# MCU_CH340.net
KiCad netlist of a schematic drawn in Altium Designer
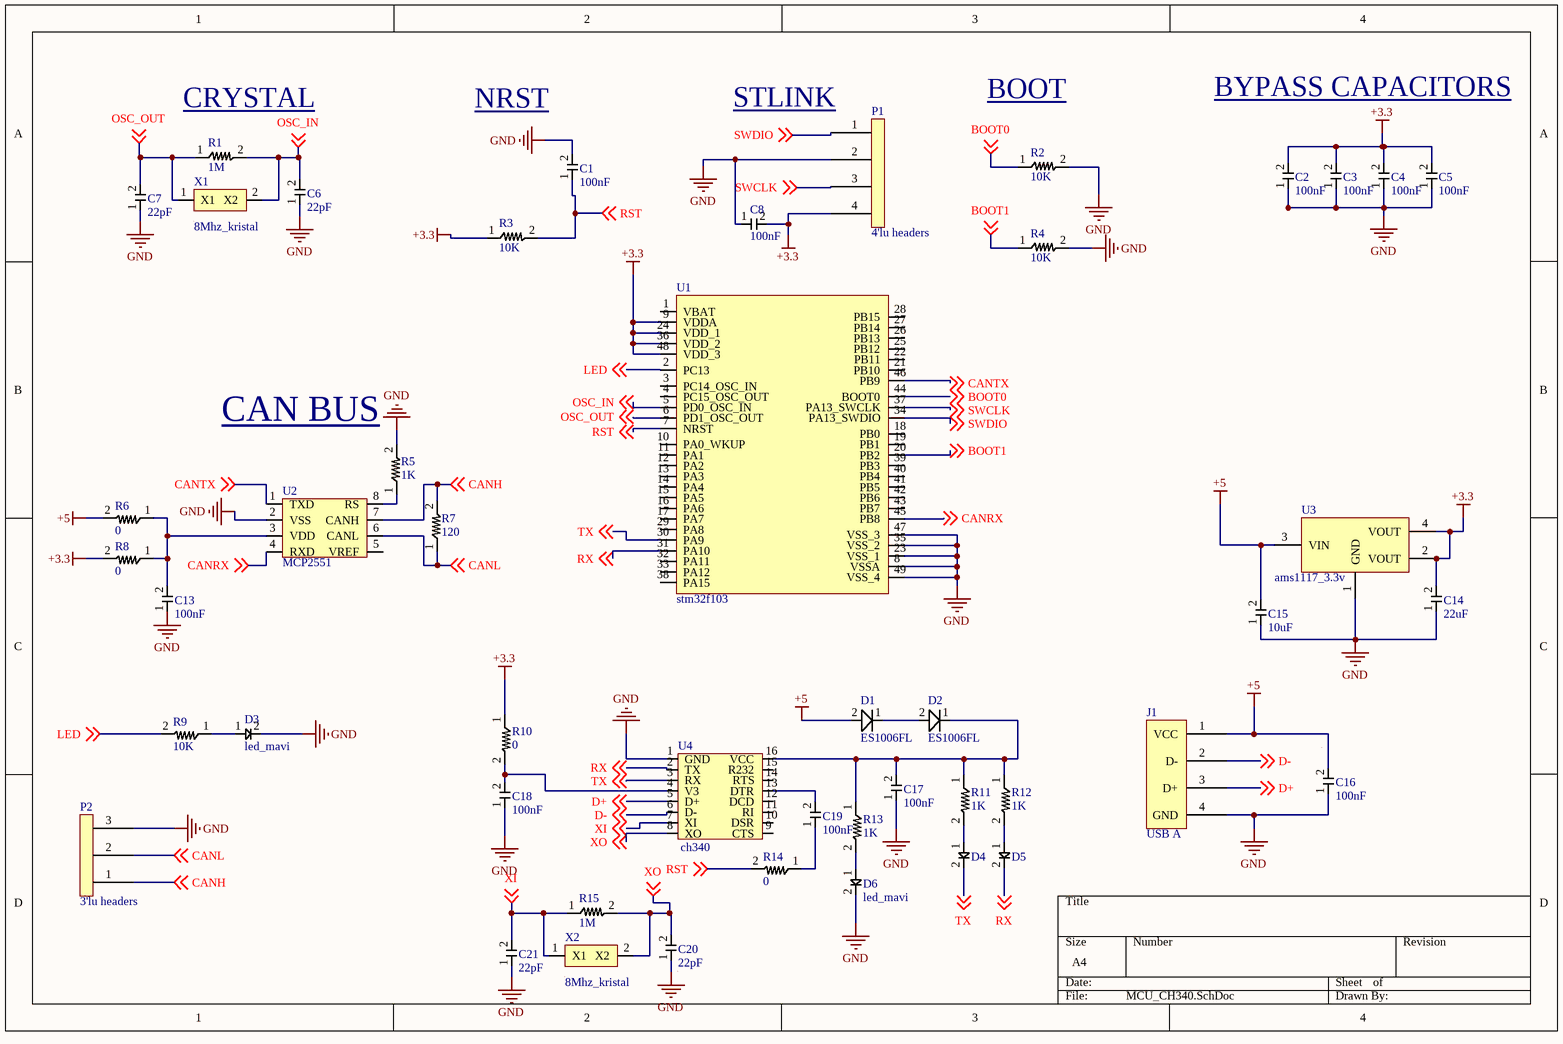
[diagram p0: MCU_CH340.SchDoc]

(export (version "E")
  (design (tool "Eeschema 10.0.6"))
  (components
    (comp (ref "C1")
      (value "100nF")
      (footprint "0805_CAP")
      (description "0805 CAPACITOR")
      (libsource (lib "smd_kompenent") (part "0805_CAP"))
    )
    (comp (ref "C2")
      (value "100nF")
      (footprint "0805_CAP")
      (description "0805 CAPACITOR")
      (libsource (lib "smd_kompenent") (part "0805_CAP"))
    )
    (comp (ref "C3")
      (value "100nF")
      (footprint "0805_CAP")
      (description "0805 CAPACITOR")
      (libsource (lib "smd_kompenent") (part "0805_CAP"))
    )
    (comp (ref "C4")
      (value "100nF")
      (footprint "0805_CAP")
      (description "0805 CAPACITOR")
      (libsource (lib "smd_kompenent") (part "0805_CAP"))
    )
    (comp (ref "C5")
      (value "100nF")
      (footprint "0805_CAP")
      (description "0805 CAPACITOR")
      (libsource (lib "smd_kompenent") (part "0805_CAP"))
    )
    (comp (ref "C6")
      (value "22pF")
      (footprint "0805_CAP")
      (description "0805 CAPACITOR")
      (libsource (lib "smd_kompenent") (part "0805_CAP"))
    )
    (comp (ref "C7")
      (value "22pF")
      (footprint "0805_CAP")
      (description "0805 CAPACITOR")
      (libsource (lib "smd_kompenent") (part "0805_CAP"))
    )
    (comp (ref "C8")
      (value "100nF")
      (footprint "0805_CAP")
      (description "0805 CAPACITOR")
      (libsource (lib "smd_kompenent") (part "0805_CAP"))
    )
    (comp (ref "C13")
      (value "100nF")
      (footprint "0805_CAP")
      (description "0805 CAPACITOR")
      (libsource (lib "smd_kompenent") (part "0805_CAP"))
    )
    (comp (ref "C14")
      (value "22uF")
      (footprint "0805_CAP")
      (description "0805 CAPACITOR")
      (libsource (lib "smd_kompenent") (part "0805_CAP"))
    )
    (comp (ref "C15")
      (value "10uF")
      (footprint "0805_CAP")
      (description "0805 CAPACITOR")
      (libsource (lib "smd_kompenent") (part "0805_CAP"))
    )
    (comp (ref "C16")
      (value "100nF")
      (footprint "0805_CAP")
      (description "0805 CAPACITOR")
      (libsource (lib "smd_kompenent") (part "0805_CAP"))
    )
    (comp (ref "C17")
      (value "100nF")
      (footprint "0805_CAP")
      (description "0805 CAPACITOR")
      (libsource (lib "smd_kompenent") (part "0805_CAP"))
    )
    (comp (ref "C18")
      (value "100nF")
      (footprint "0805_CAP")
      (description "0805 CAPACITOR")
      (libsource (lib "smd_kompenent") (part "0805_CAP"))
    )
    (comp (ref "C19")
      (value "100nF")
      (footprint "0805_CAP")
      (description "0805 CAPACITOR")
      (libsource (lib "smd_kompenent") (part "0805_CAP"))
    )
    (comp (ref "C20")
      (value "22pF")
      (footprint "0805_CAP")
      (description "0805 CAPACITOR")
      (libsource (lib "smd_kompenent") (part "0805_CAP"))
    )
    (comp (ref "C21")
      (value "22pF")
      (footprint "0805_CAP")
      (description "0805 CAPACITOR")
      (libsource (lib "smd_kompenent") (part "0805_CAP"))
    )
    (comp (ref "D1")
      (value "ES1006FL")
      (footprint "ES1006FL")
      (description "ES1006FL 1A 600V Diyot Fred Ultra Hızlı")
      (libsource (lib "smd_kompenent") (part "ES1006FL"))
    )
    (comp (ref "D2")
      (value "ES1006FL")
      (footprint "ES1006FL")
      (description "ES1006FL 1A 600V Diyot Fred Ultra Hızlı")
      (libsource (lib "smd_kompenent") (part "ES1006FL"))
    )
    (comp (ref "D3")
      (value "led_mavi")
      (footprint "led")
      (description "0805 mavi led")
      (libsource (lib "smd_kompenent") (part "led_mavi"))
    )
    (comp (ref "D4")
      (value "~")
      (footprint "led")
      (description "0805 mavi led")
      (libsource (lib "smd_kompenent") (part "led_mavi"))
    )
    (comp (ref "D5")
      (value "~")
      (footprint "led")
      (description "0805 mavi led")
      (libsource (lib "smd_kompenent") (part "led_mavi"))
    )
    (comp (ref "D6")
      (value "led_mavi")
      (footprint "led")
      (description "0805 mavi led")
      (libsource (lib "smd_kompenent") (part "led_mavi"))
    )
    (comp (ref "J1") (value "USB A") (footprint "USB A") (libsource (lib "dip_kompenent") (part "USB A")))
    (comp (ref "P1")
      (value "4'lu headers")
      (footprint "4'lu headers")
      (libsource (lib "dip_kompenent") (part "4'lu headers"))
    )
    (comp (ref "P2")
      (value "3'lu headers")
      (footprint "3'lu headers")
      (libsource (lib "dip_kompenent") (part "3'lu headers"))
    )
    (comp (ref "R1")
      (value "1M")
      (footprint "res_0805")
      (description "0805")
      (libsource (lib "smd_kompenent") (part "0805_RES"))
    )
    (comp (ref "R2")
      (value "10K")
      (footprint "res_0805")
      (description "0805")
      (libsource (lib "smd_kompenent") (part "0805_RES"))
    )
    (comp (ref "R3")
      (value "10K")
      (footprint "res_0805")
      (description "0805")
      (libsource (lib "smd_kompenent") (part "0805_RES"))
    )
    (comp (ref "R4")
      (value "10K")
      (footprint "res_0805")
      (description "0805")
      (libsource (lib "smd_kompenent") (part "0805_RES"))
    )
    (comp (ref "R5")
      (value "1K")
      (footprint "res_0805")
      (description "0805")
      (libsource (lib "smd_kompenent") (part "0805_RES"))
    )
    (comp (ref "R6")
      (value "0")
      (footprint "res_0805")
      (description "0805")
      (libsource (lib "smd_kompenent") (part "0805_RES"))
    )
    (comp (ref "R7")
      (value "120")
      (footprint "res_0805")
      (description "0805")
      (libsource (lib "smd_kompenent") (part "0805_RES"))
    )
    (comp (ref "R8")
      (value "0")
      (footprint "res_0805")
      (description "0805")
      (libsource (lib "smd_kompenent") (part "0805_RES"))
    )
    (comp (ref "R9")
      (value "10K")
      (footprint "res_0805")
      (description "0805")
      (libsource (lib "smd_kompenent") (part "0805_RES"))
    )
    (comp (ref "R10")
      (value "0")
      (footprint "res_0805")
      (description "0805")
      (libsource (lib "smd_kompenent") (part "0805_RES"))
    )
    (comp (ref "R11")
      (value "1K")
      (footprint "res_0805")
      (description "0805")
      (libsource (lib "smd_kompenent") (part "0805_RES"))
    )
    (comp (ref "R12")
      (value "1K")
      (footprint "res_0805")
      (description "0805")
      (libsource (lib "smd_kompenent") (part "0805_RES"))
    )
    (comp (ref "R13")
      (value "1K")
      (footprint "res_0805")
      (description "0805")
      (libsource (lib "smd_kompenent") (part "0805_RES"))
    )
    (comp (ref "R14")
      (value "0")
      (footprint "res_0805")
      (description "0805")
      (libsource (lib "smd_kompenent") (part "0805_RES"))
    )
    (comp (ref "R15")
      (value "1M")
      (footprint "res_0805")
      (description "0805")
      (libsource (lib "smd_kompenent") (part "0805_RES"))
    )
    (comp (ref "U1")
      (value "stm32f103")
      (footprint "STM32F103C6T8")
      (description "STM MCU")
      (libsource (lib "smd_kompenent") (part "stm32f103"))
    )
    (comp (ref "U2")
      (value "MCP2551")
      (footprint "SOIC-8")
      (description "SOIC-8")
      (libsource (lib "smd_kompenent") (part "MCP2551"))
    )
    (comp (ref "U3")
      (value "ams1117_3.3v")
      (footprint "ams1117")
      (libsource (lib "smd_kompenent") (part "ams1117_3.3v"))
    )
    (comp (ref "U4")
      (value "ch340")
      (footprint "CH340 SOIC16")
      (libsource (lib "smd_kompenent") (part "ch340"))
    )
    (comp (ref "X1")
      (value "8Mhz_kristal")
      (footprint "8mhz_kristal")
      (description "2 pin kristal")
      (libsource (lib "smd_kompenent") (part "8Mhz_kristal"))
    )
    (comp (ref "X2")
      (value "8Mhz_kristal")
      (footprint "8mhz_kristal")
      (description "2 pin kristal")
      (libsource (lib "smd_kompenent") (part "8Mhz_kristal"))
    )
  )
  (nets
    (net (code "1") (name "+3.3") (class "Default")
      (node (ref "C14") (pin "2") (pintype "passive"))
      (node (ref "C2") (pin "2") (pintype "passive"))
      (node (ref "C3") (pin "2") (pintype "passive"))
      (node (ref "C4") (pin "2") (pintype "passive"))
      (node (ref "C5") (pin "2") (pintype "passive"))
      (node (ref "C8") (pin "2") (pintype "passive"))
      (node (ref "P1") (pin "4") (pintype "passive"))
      (node (ref "R10") (pin "1") (pintype "passive"))
      (node (ref "R3") (pin "1") (pintype "passive"))
      (node (ref "R8") (pin "2") (pintype "passive"))
      (node (ref "U1") (pin "24") (pinfunction "VDD_1_24") (pintype "passive"))
      (node (ref "U1") (pin "36") (pinfunction "VDD_2_36") (pintype "passive"))
      (node (ref "U1") (pin "48") (pinfunction "VDD_3_48") (pintype "passive"))
      (node (ref "U1") (pin "9") (pinfunction "VDDA_9") (pintype "passive"))
      (node (ref "U3") (pin "2") (pinfunction "VOUT_2") (pintype "passive"))
      (node (ref "U3") (pin "4") (pinfunction "VOUT_4") (pintype "passive"))
    )
    (net (code "2") (name "+5") (class "Default")
      (node (ref "C15") (pin "2") (pintype "passive"))
      (node (ref "C16") (pin "2") (pintype "passive"))
      (node (ref "D1") (pin "2") (pintype "passive"))
      (node (ref "J1") (pin "1") (pinfunction "VCC_1") (pintype "passive"))
      (node (ref "R6") (pin "2") (pintype "passive"))
      (node (ref "U3") (pin "3") (pinfunction "VIN_3") (pintype "passive"))
    )
    (net (code "3") (name "BOOT0") (class "Default")
      (node (ref "R2") (pin "1") (pintype "passive"))
      (node (ref "U1") (pin "44") (pinfunction "BOOT0_44") (pintype "passive"))
    )
    (net (code "4") (name "BOOT1") (class "Default")
      (node (ref "R4") (pin "1") (pintype "passive"))
      (node (ref "U1") (pin "20") (pinfunction "PB2_20") (pintype "passive"))
    )
    (net (code "5") (name "CANH") (class "Default")
      (node (ref "P2") (pin "1") (pintype "passive"))
      (node (ref "R7") (pin "2") (pintype "passive"))
      (node (ref "U2") (pin "7") (pinfunction "CANH_7") (pintype "passive"))
    )
    (net (code "6") (name "CANL") (class "Default")
      (node (ref "P2") (pin "2") (pintype "passive"))
      (node (ref "R7") (pin "1") (pintype "passive"))
      (node (ref "U2") (pin "6") (pinfunction "CANL_6") (pintype "passive"))
    )
    (net (code "7") (name "CANRX") (class "Default")
      (node (ref "U1") (pin "45") (pinfunction "PB8_45") (pintype "passive"))
      (node (ref "U2") (pin "4") (pinfunction "RXD_4") (pintype "passive"))
    )
    (net (code "8") (name "CANTX") (class "Default")
      (node (ref "U1") (pin "46") (pinfunction "PB9_46") (pintype "passive"))
      (node (ref "U2") (pin "1") (pinfunction "TXD_1") (pintype "passive"))
    )
    (net (code "9") (name "D+") (class "Default")
      (node (ref "J1") (pin "3") (pinfunction "D+_3") (pintype "passive"))
      (node (ref "U4") (pin "5") (pinfunction "D+_5") (pintype "passive"))
    )
    (net (code "10") (name "D-") (class "Default")
      (node (ref "J1") (pin "2") (pinfunction "D-_2") (pintype "passive"))
      (node (ref "U4") (pin "6") (pinfunction "D-_6") (pintype "passive"))
    )
    (net (code "11") (name "GND") (class "Default")
      (node (ref "C1") (pin "2") (pintype "passive"))
      (node (ref "C13") (pin "1") (pintype "passive"))
      (node (ref "C14") (pin "1") (pintype "passive"))
      (node (ref "C15") (pin "1") (pintype "passive"))
      (node (ref "C16") (pin "1") (pintype "passive"))
      (node (ref "C17") (pin "1") (pintype "passive"))
      (node (ref "C18") (pin "1") (pintype "passive"))
      (node (ref "C2") (pin "1") (pintype "passive"))
      (node (ref "C20") (pin "1") (pintype "passive"))
      (node (ref "C21") (pin "1") (pintype "passive"))
      (node (ref "C3") (pin "1") (pintype "passive"))
      (node (ref "C4") (pin "1") (pintype "passive"))
      (node (ref "C5") (pin "1") (pintype "passive"))
      (node (ref "C6") (pin "1") (pintype "passive"))
      (node (ref "C7") (pin "1") (pintype "passive"))
      (node (ref "C8") (pin "1") (pintype "passive"))
      (node (ref "D3") (pin "2") (pintype "passive"))
      (node (ref "D6") (pin "2") (pintype "passive"))
      (node (ref "J1") (pin "4") (pinfunction "GND_4") (pintype "passive"))
      (node (ref "P1") (pin "2") (pintype "passive"))
      (node (ref "P2") (pin "3") (pintype "passive"))
      (node (ref "R2") (pin "2") (pintype "passive"))
      (node (ref "R4") (pin "2") (pintype "passive"))
      (node (ref "R5") (pin "2") (pintype "passive"))
      (node (ref "U1") (pin "23") (pinfunction "VSS_1_23") (pintype "passive"))
      (node (ref "U1") (pin "35") (pinfunction "VSS_2_35") (pintype "passive"))
      (node (ref "U1") (pin "47") (pinfunction "VSS_3_47") (pintype "passive"))
      (node (ref "U1") (pin "49") (pinfunction "VSS_4_49") (pintype "passive"))
      (node (ref "U1") (pin "8") (pinfunction "VSSA_8") (pintype "passive"))
      (node (ref "U2") (pin "2") (pinfunction "VSS_2") (pintype "passive"))
      (node (ref "U3") (pin "1") (pinfunction "GND_1") (pintype "passive"))
      (node (ref "U4") (pin "1") (pinfunction "GND_1") (pintype "passive"))
    )
    (net (code "12") (name "LED") (class "Default")
      (node (ref "R9") (pin "2") (pintype "passive"))
      (node (ref "U1") (pin "2") (pinfunction "PC13_2") (pintype "passive"))
    )
    (net (code "13") (name "Net-(C19-Pad1)") (class "Default")
      (node (ref "C19") (pin "1") (pintype "passive"))
      (node (ref "R14") (pin "1") (pintype "passive"))
    )
    (net (code "14") (name "Net-(D1-Pad1)") (class "Default")
      (node (ref "D1") (pin "1") (pintype "passive"))
      (node (ref "D2") (pin "2") (pintype "passive"))
    )
    (net (code "15") (name "Net-(D3-Pad1)") (class "Default")
      (node (ref "D3") (pin "1") (pintype "passive"))
      (node (ref "R9") (pin "1") (pintype "passive"))
    )
    (net (code "16") (name "Net-(D4-Pad1)") (class "Default")
      (node (ref "D4") (pin "1") (pintype "passive"))
      (node (ref "R11") (pin "2") (pintype "passive"))
    )
    (net (code "17") (name "Net-(D5-Pad1)") (class "Default")
      (node (ref "D5") (pin "1") (pintype "passive"))
      (node (ref "R12") (pin "2") (pintype "passive"))
    )
    (net (code "18") (name "Net-(D6-Pad1)") (class "Default")
      (node (ref "D6") (pin "1") (pintype "passive"))
      (node (ref "R13") (pin "2") (pintype "passive"))
    )
    (net (code "19") (name "Net-(U2-RS)") (class "Default")
      (node (ref "R5") (pin "1") (pintype "passive"))
      (node (ref "U2") (pin "8") (pinfunction "RS_8") (pintype "passive"))
    )
    (net (code "20") (name "Net-(U2-VDD)") (class "Default")
      (node (ref "C13") (pin "2") (pintype "passive"))
      (node (ref "R6") (pin "1") (pintype "passive"))
      (node (ref "R8") (pin "1") (pintype "passive"))
      (node (ref "U2") (pin "3") (pinfunction "VDD_3") (pintype "passive"))
    )
    (net (code "21") (name "Net-(U4-DTR)") (class "Default")
      (node (ref "C19") (pin "2") (pintype "passive"))
      (node (ref "U4") (pin "13") (pinfunction "DTR_13") (pintype "passive"))
    )
    (net (code "22") (name "Net-(U4-V3)") (class "Default")
      (node (ref "C18") (pin "2") (pintype "passive"))
      (node (ref "R10") (pin "2") (pintype "passive"))
      (node (ref "U4") (pin "4") (pinfunction "V3_4") (pintype "passive"))
    )
    (net (code "23") (name "Net-(U4-VCC)") (class "Default")
      (node (ref "C17") (pin "2") (pintype "passive"))
      (node (ref "D2") (pin "1") (pintype "passive"))
      (node (ref "R11") (pin "1") (pintype "passive"))
      (node (ref "R12") (pin "1") (pintype "passive"))
      (node (ref "R13") (pin "1") (pintype "passive"))
      (node (ref "U4") (pin "16") (pinfunction "VCC_16") (pintype "passive"))
    )
    (net (code "24") (name "OSC_IN") (class "Default")
      (node (ref "C6") (pin "2") (pintype "passive"))
      (node (ref "R1") (pin "2") (pintype "passive"))
      (node (ref "U1") (pin "5") (pinfunction "PD0_OSC_IN_5") (pintype "passive"))
      (node (ref "X1") (pin "2") (pinfunction "X2_2") (pintype "passive"))
    )
    (net (code "25") (name "OSC_OUT") (class "Default")
      (node (ref "C7") (pin "2") (pintype "passive"))
      (node (ref "R1") (pin "1") (pintype "passive"))
      (node (ref "U1") (pin "6") (pinfunction "PD1_OSC_OUT_6") (pintype "passive"))
      (node (ref "X1") (pin "1") (pinfunction "X1_1") (pintype "passive"))
    )
    (net (code "26") (name "RST") (class "Default")
      (node (ref "C1") (pin "1") (pintype "passive"))
      (node (ref "R14") (pin "2") (pintype "passive"))
      (node (ref "R3") (pin "2") (pintype "passive"))
      (node (ref "U1") (pin "7") (pinfunction "NRST_7") (pintype "passive"))
    )
    (net (code "27") (name "RX") (class "Default")
      (node (ref "D5") (pin "2") (pintype "passive"))
      (node (ref "U1") (pin "31") (pinfunction "PA10_31") (pintype "passive"))
      (node (ref "U4") (pin "2") (pinfunction "TX_2") (pintype "passive"))
    )
    (net (code "28") (name "SWCLK") (class "Default")
      (node (ref "P1") (pin "3") (pintype "passive"))
      (node (ref "U1") (pin "37") (pinfunction "PA13_SWCLK_37") (pintype "passive"))
    )
    (net (code "29") (name "SWDIO") (class "Default")
      (node (ref "P1") (pin "1") (pintype "passive"))
      (node (ref "U1") (pin "34") (pinfunction "PA13_SWDIO_34") (pintype "passive"))
    )
    (net (code "30") (name "TX") (class "Default")
      (node (ref "D4") (pin "2") (pintype "passive"))
      (node (ref "U1") (pin "30") (pinfunction "PA9_30") (pintype "passive"))
      (node (ref "U4") (pin "3") (pinfunction "RX_3") (pintype "passive"))
    )
    (net (code "31") (name "XI") (class "Default")
      (node (ref "C21") (pin "2") (pintype "passive"))
      (node (ref "R15") (pin "1") (pintype "passive"))
      (node (ref "U4") (pin "7") (pinfunction "XI_7") (pintype "passive"))
      (node (ref "X2") (pin "1") (pinfunction "X1_1") (pintype "passive"))
    )
    (net (code "32") (name "XO") (class "Default")
      (node (ref "C20") (pin "2") (pintype "passive"))
      (node (ref "R15") (pin "2") (pintype "passive"))
      (node (ref "U4") (pin "8") (pinfunction "XO_8") (pintype "passive"))
      (node (ref "X2") (pin "2") (pinfunction "X2_2") (pintype "passive"))
    )
    (net (code "33") (name "unconnected-(U1-PA0_WKUP-Pad10)") (class "Default")
      (node (ref "U1") (pin "10") (pinfunction "PA0_WKUP_10") (pintype "passive"))
    )
    (net (code "34") (name "unconnected-(U1-PA1-Pad11)") (class "Default")
      (node (ref "U1") (pin "11") (pinfunction "PA1_11") (pintype "passive"))
    )
    (net (code "35") (name "unconnected-(U1-PA2-Pad12)") (class "Default")
      (node (ref "U1") (pin "12") (pinfunction "PA2_12") (pintype "passive"))
    )
    (net (code "36") (name "unconnected-(U1-PA3-Pad13)") (class "Default")
      (node (ref "U1") (pin "13") (pinfunction "PA3_13") (pintype "passive"))
    )
    (net (code "37") (name "unconnected-(U1-PA4-Pad14)") (class "Default")
      (node (ref "U1") (pin "14") (pinfunction "PA4_14") (pintype "passive"))
    )
    (net (code "38") (name "unconnected-(U1-PA5-Pad15)") (class "Default")
      (node (ref "U1") (pin "15") (pinfunction "PA5_15") (pintype "passive"))
    )
    (net (code "39") (name "unconnected-(U1-PA6-Pad16)") (class "Default")
      (node (ref "U1") (pin "16") (pinfunction "PA6_16") (pintype "passive"))
    )
    (net (code "40") (name "unconnected-(U1-PA7-Pad17)") (class "Default")
      (node (ref "U1") (pin "17") (pinfunction "PA7_17") (pintype "passive"))
    )
    (net (code "41") (name "unconnected-(U1-PA8-Pad29)") (class "Default")
      (node (ref "U1") (pin "29") (pinfunction "PA8_29") (pintype "passive"))
    )
    (net (code "42") (name "unconnected-(U1-PA11-Pad32)") (class "Default")
      (node (ref "U1") (pin "32") (pinfunction "PA11_32") (pintype "passive"))
    )
    (net (code "43") (name "unconnected-(U1-PA12-Pad33)") (class "Default")
      (node (ref "U1") (pin "33") (pinfunction "PA12_33") (pintype "passive"))
    )
    (net (code "44") (name "unconnected-(U1-PA15-Pad38)") (class "Default")
      (node (ref "U1") (pin "38") (pinfunction "PA15_38") (pintype "passive"))
    )
    (net (code "45") (name "unconnected-(U1-PB0-Pad18)") (class "Default")
      (node (ref "U1") (pin "18") (pinfunction "PB0_18") (pintype "passive"))
    )
    (net (code "46") (name "unconnected-(U1-PB1-Pad19)") (class "Default")
      (node (ref "U1") (pin "19") (pinfunction "PB1_19") (pintype "passive"))
    )
    (net (code "47") (name "unconnected-(U1-PB3-Pad39)") (class "Default")
      (node (ref "U1") (pin "39") (pinfunction "PB3_39") (pintype "passive"))
    )
    (net (code "48") (name "unconnected-(U1-PB4-Pad40)") (class "Default")
      (node (ref "U1") (pin "40") (pinfunction "PB4_40") (pintype "passive"))
    )
    (net (code "49") (name "unconnected-(U1-PB5-Pad41)") (class "Default")
      (node (ref "U1") (pin "41") (pinfunction "PB5_41") (pintype "passive"))
    )
    (net (code "50") (name "unconnected-(U1-PB6-Pad42)") (class "Default")
      (node (ref "U1") (pin "42") (pinfunction "PB6_42") (pintype "passive"))
    )
    (net (code "51") (name "unconnected-(U1-PB7-Pad43)") (class "Default")
      (node (ref "U1") (pin "43") (pinfunction "PB7_43") (pintype "passive"))
    )
    (net (code "52") (name "unconnected-(U1-PB10-Pad21)") (class "Default")
      (node (ref "U1") (pin "21") (pinfunction "PB10_21") (pintype "passive"))
    )
    (net (code "53") (name "unconnected-(U1-PB11-Pad22)") (class "Default")
      (node (ref "U1") (pin "22") (pinfunction "PB11_22") (pintype "passive"))
    )
    (net (code "54") (name "unconnected-(U1-PB12-Pad25)") (class "Default")
      (node (ref "U1") (pin "25") (pinfunction "PB12_25") (pintype "passive"))
    )
    (net (code "55") (name "unconnected-(U1-PB13-Pad26)") (class "Default")
      (node (ref "U1") (pin "26") (pinfunction "PB13_26") (pintype "passive"))
    )
    (net (code "56") (name "unconnected-(U1-PB14-Pad27)") (class "Default")
      (node (ref "U1") (pin "27") (pinfunction "PB14_27") (pintype "passive"))
    )
    (net (code "57") (name "unconnected-(U1-PB15-Pad28)") (class "Default")
      (node (ref "U1") (pin "28") (pinfunction "PB15_28") (pintype "passive"))
    )
    (net (code "58") (name "unconnected-(U1-PC14_OSC_IN-Pad3)") (class "Default")
      (node (ref "U1") (pin "3") (pinfunction "PC14_OSC_IN_3") (pintype "passive"))
    )
    (net (code "59") (name "unconnected-(U1-PC15_OSC_OUT-Pad4)") (class "Default")
      (node (ref "U1") (pin "4") (pinfunction "PC15_OSC_OUT_4") (pintype "passive"))
    )
    (net (code "60") (name "unconnected-(U1-VBAT-Pad1)") (class "Default")
      (node (ref "U1") (pin "1") (pinfunction "VBAT_1") (pintype "passive"))
    )
    (net (code "61") (name "unconnected-(U2-VREF-Pad5)") (class "Default")
      (node (ref "U2") (pin "5") (pinfunction "VREF_5") (pintype "passive"))
    )
    (net (code "62") (name "unconnected-(U4-CTS-Pad9)") (class "Default")
      (node (ref "U4") (pin "9") (pinfunction "CTS_9") (pintype "passive"))
    )
    (net (code "63") (name "unconnected-(U4-DCD-Pad12)") (class "Default")
      (node (ref "U4") (pin "12") (pinfunction "DCD_12") (pintype "passive"))
    )
    (net (code "64") (name "unconnected-(U4-DSR-Pad10)") (class "Default")
      (node (ref "U4") (pin "10") (pinfunction "DSR_10") (pintype "passive"))
    )
    (net (code "65") (name "unconnected-(U4-R232-Pad15)") (class "Default")
      (node (ref "U4") (pin "15") (pinfunction "R232_15") (pintype "passive"))
    )
    (net (code "66") (name "unconnected-(U4-RI-Pad11)") (class "Default")
      (node (ref "U4") (pin "11") (pinfunction "RI_11") (pintype "passive"))
    )
    (net (code "67") (name "unconnected-(U4-RTS-Pad14)") (class "Default")
      (node (ref "U4") (pin "14") (pinfunction "RTS_14") (pintype "passive"))
    )
  )
)
